# Marvin_1_0.net
KiCad netlist of a schematic drawn in EAGLE
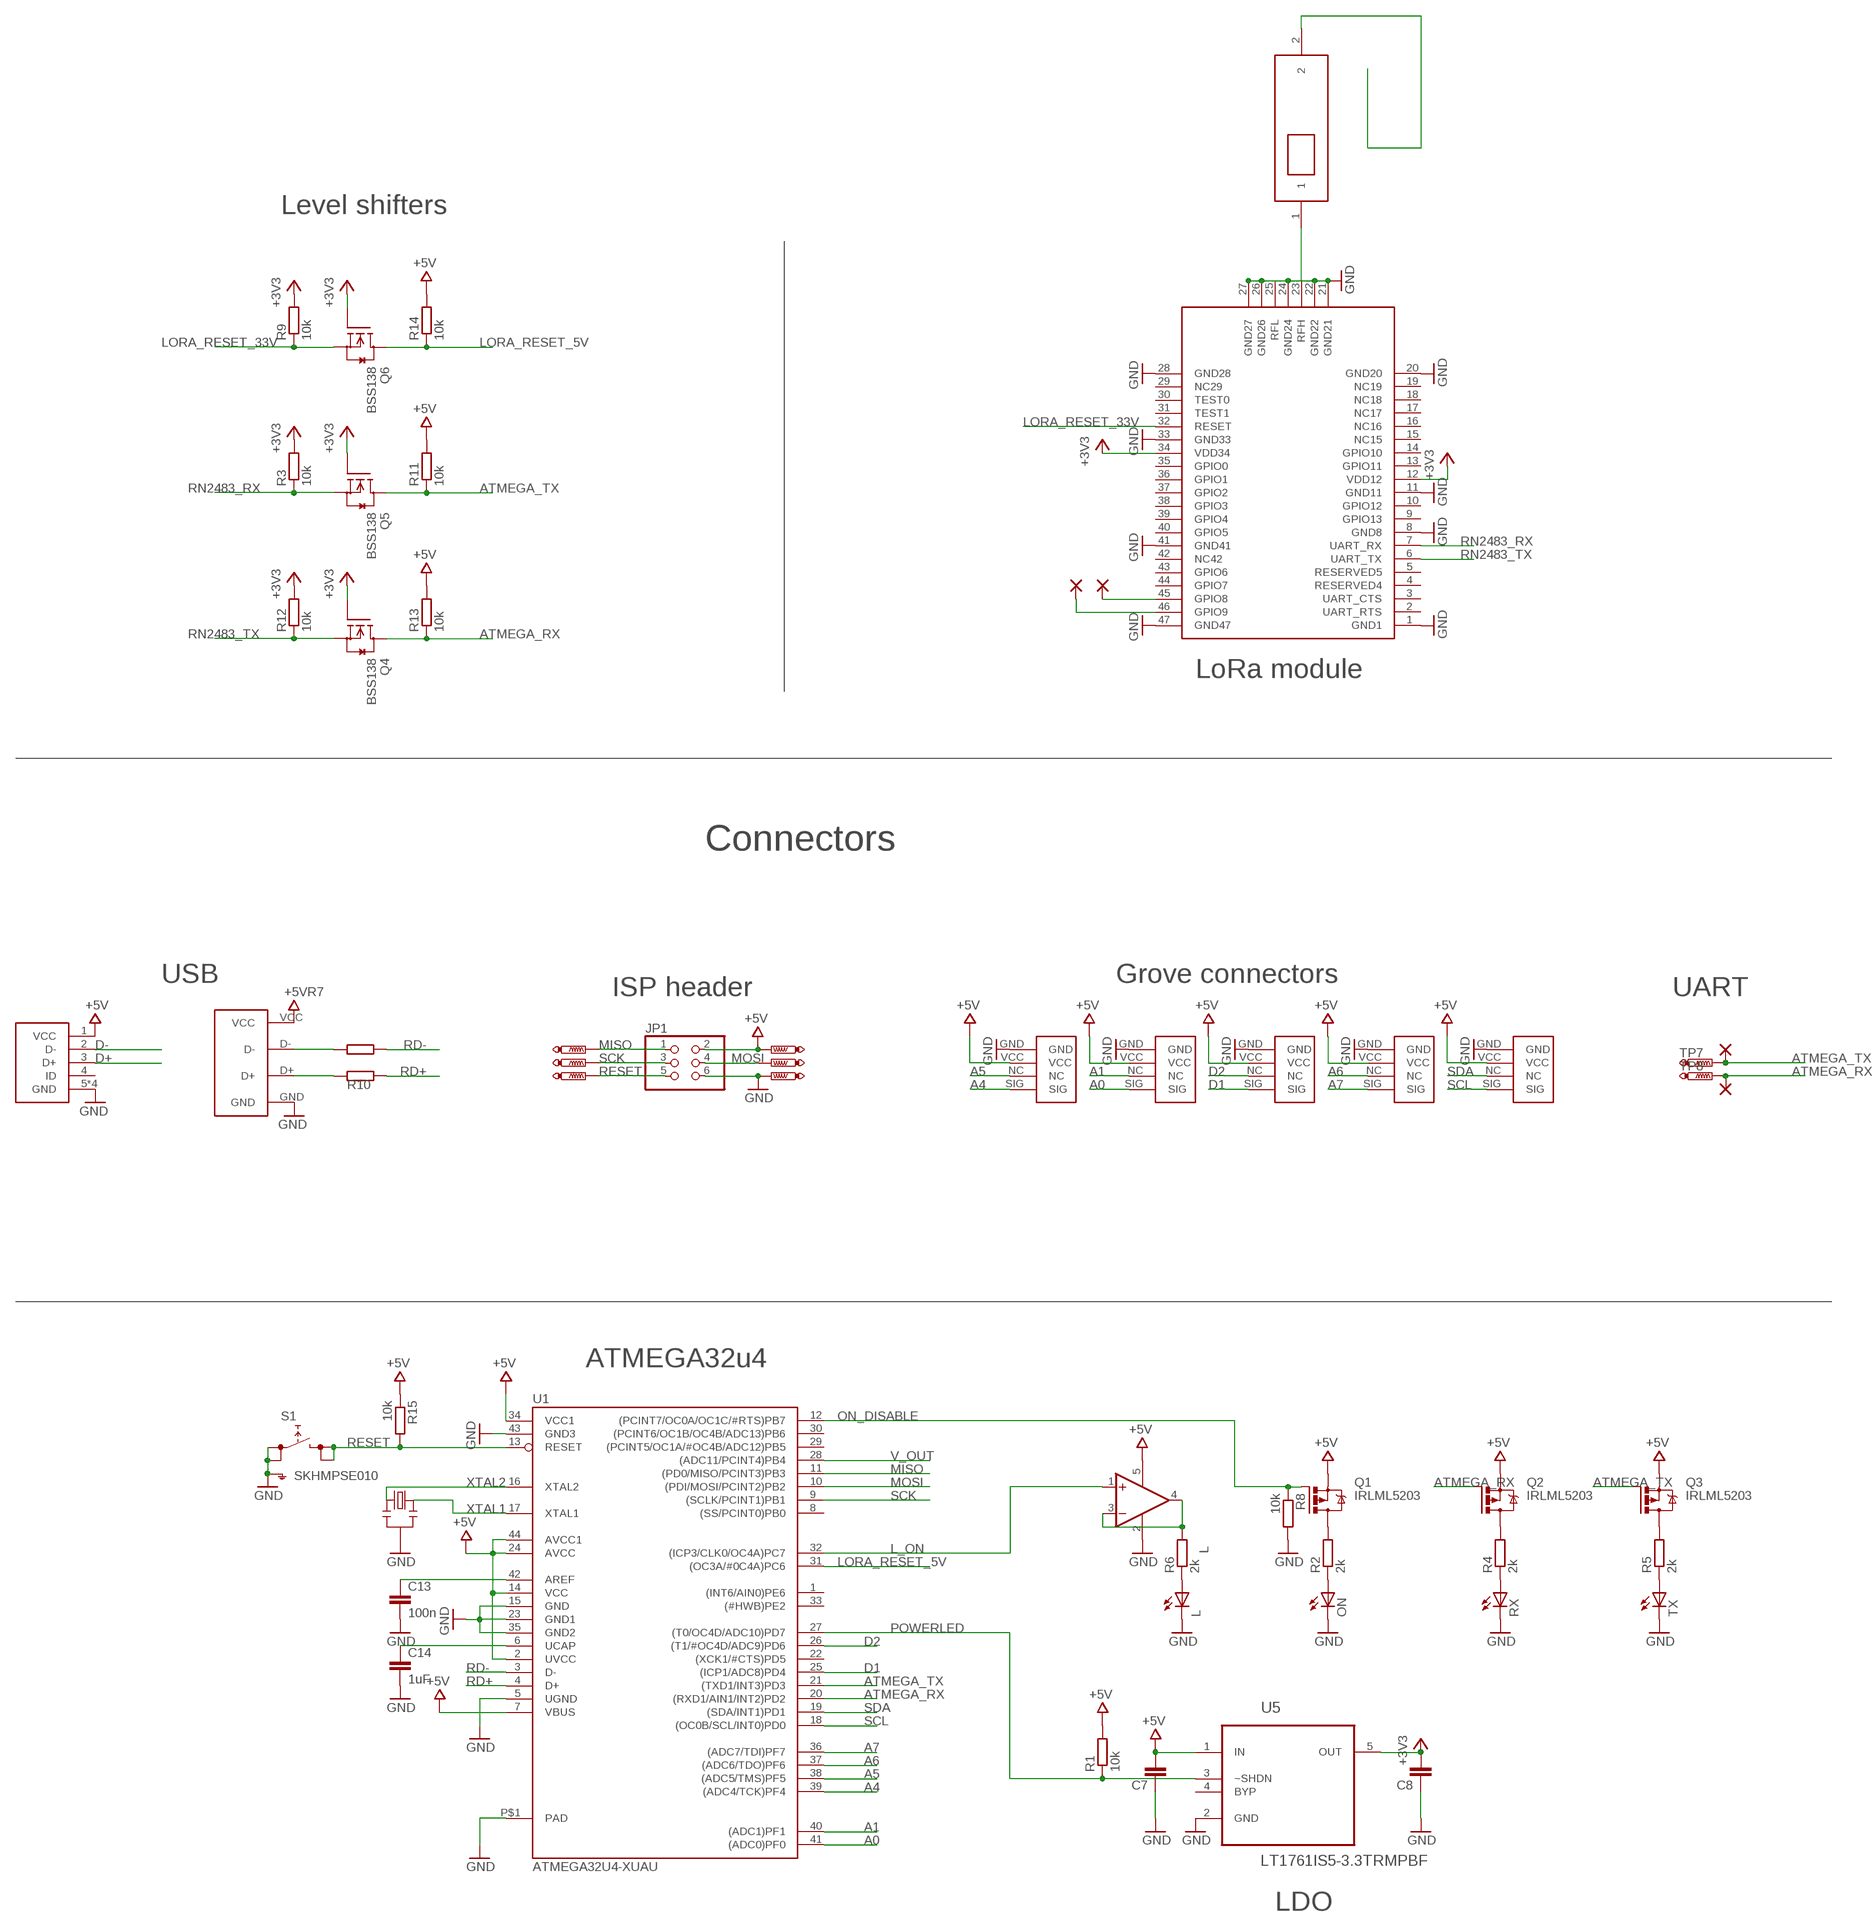
[diagram p0: schematic, sheet 1]

(export (version "E")
  (design (tool "Eeschema 10.0.6"))
  (components
    (comp (ref "A1")
      (value "GROVE")
      (footprint "eagle-import:4POS2MM")
      (libsource (lib "eagle-import") (part "GROVE"))
    )
    (comp (ref "A2")
      (value "GROVE")
      (footprint "eagle-import:4POS2MM")
      (libsource (lib "eagle-import") (part "GROVE"))
    )
    (comp (ref "A3")
      (value "GROVE")
      (footprint "eagle-import:4POS2MM")
      (libsource (lib "eagle-import") (part "GROVE"))
    )
    (comp (ref "C7")
      (value "C-EUC0603")
      (footprint "eagle-import:C0603")
      (libsource (lib "eagle-import") (part "rcl_C-EUC0603"))
    )
    (comp (ref "C8")
      (value "C-EUC0603")
      (footprint "eagle-import:C0603")
      (libsource (lib "eagle-import") (part "rcl_C-EUC0603"))
    )
    (comp (ref "C13")
      (value "100n")
      (footprint "eagle-import:C0603K")
      (libsource (lib "eagle-import") (part "C-EUC0603K"))
    )
    (comp (ref "C14")
      (value "1uF")
      (footprint "eagle-import:C0603K")
      (libsource (lib "eagle-import") (part "C-EUC0603K"))
    )
    (comp (ref "D2")
      (value "GROVE")
      (footprint "eagle-import:4POS2MM")
      (libsource (lib "eagle-import") (part "GROVE"))
    )
    (comp (ref "D2/I2C")
      (value "GROVE")
      (footprint "eagle-import:4POS2MM")
      (libsource (lib "eagle-import") (part "GROVE"))
    )
    (comp (ref "IC1")
      (value "LM321MF")
      (footprint "eagle-import:SOT23-5")
      (libsource (lib "eagle-import") (part "LM321?MF"))
    )
    (comp (ref "JP1")
      (value "PINHD-2X3")
      (footprint "eagle-import:2X03")
      (libsource (lib "eagle-import") (part "PINHD-2X3"))
    )
    (comp (ref "L")
      (value "LEDSML0603")
      (footprint "eagle-import:SML0603")
      (libsource (lib "eagle-import") (part "LEDSML0603"))
    )
    (comp (ref "ON")
      (value "LEDSML0603")
      (footprint "eagle-import:SML0603")
      (libsource (lib "eagle-import") (part "LEDSML0603"))
    )
    (comp (ref "PAD1")
      (value "WIREPAD1,6/0,9")
      (footprint "eagle-import:1,6_0,9")
      (libsource (lib "eagle-import") (part "WIREPAD1,6/0,9"))
    )
    (comp (ref "PAD2")
      (value "WIREPAD1,6/0,9")
      (footprint "eagle-import:1,6_0,9")
      (libsource (lib "eagle-import") (part "WIREPAD1,6/0,9"))
    )
    (comp (ref "PAD3")
      (value "WIREPAD1,6/0,9")
      (footprint "eagle-import:1,6_0,9")
      (libsource (lib "eagle-import") (part "WIREPAD1,6/0,9"))
    )
    (comp (ref "PAD4")
      (value "WIREPAD1,6/0,9")
      (footprint "eagle-import:1,6_0,9")
      (libsource (lib "eagle-import") (part "WIREPAD1,6/0,9"))
    )
    (comp (ref "Q1")
      (value "IRLML5203")
      (footprint "eagle-import:MICRO3")
      (libsource (lib "eagle-import") (part "IRLML5203"))
    )
    (comp (ref "Q2")
      (value "IRLML5203")
      (footprint "eagle-import:MICRO3")
      (libsource (lib "eagle-import") (part "IRLML5203"))
    )
    (comp (ref "Q3")
      (value "IRLML5203")
      (footprint "eagle-import:MICRO3")
      (libsource (lib "eagle-import") (part "IRLML5203"))
    )
    (comp (ref "Q4")
      (value "BSS138")
      (footprint "eagle-import:SOT23")
      (libsource (lib "eagle-import") (part "BSS138"))
    )
    (comp (ref "Q5")
      (value "BSS138")
      (footprint "eagle-import:SOT23")
      (libsource (lib "eagle-import") (part "BSS138"))
    )
    (comp (ref "Q6")
      (value "BSS138")
      (footprint "eagle-import:SOT23")
      (libsource (lib "eagle-import") (part "BSS138"))
    )
    (comp (ref "R1")
      (value "10k")
      (footprint "eagle-import:R0603")
      (libsource (lib "eagle-import") (part "rcl_R-EU_R0603"))
    )
    (comp (ref "R2")
      (value "2k")
      (footprint "eagle-import:R0603")
      (libsource (lib "eagle-import") (part "rcl_R-EU_R0603"))
    )
    (comp (ref "R3")
      (value "10k")
      (footprint "eagle-import:R0603")
      (libsource (lib "eagle-import") (part "rcl_R-EU_R0603"))
    )
    (comp (ref "R4")
      (value "2k")
      (footprint "eagle-import:R0603")
      (libsource (lib "eagle-import") (part "rcl_R-EU_R0603"))
    )
    (comp (ref "R5")
      (value "2k")
      (footprint "eagle-import:R0603")
      (libsource (lib "eagle-import") (part "rcl_R-EU_R0603"))
    )
    (comp (ref "R6")
      (value "2k")
      (footprint "eagle-import:R0603")
      (libsource (lib "eagle-import") (part "rcl_R-EU_R0603"))
    )
    (comp (ref "R7")
      (value "30")
      (footprint "eagle-import:R0603-ROUND")
      (libsource (lib "eagle-import") (part "R-EU_R0603"))
    )
    (comp (ref "R8")
      (value "10k")
      (footprint "eagle-import:R0603")
      (libsource (lib "eagle-import") (part "rcl_R-EU_R0603"))
    )
    (comp (ref "R9")
      (value "10k")
      (footprint "eagle-import:R0603")
      (libsource (lib "eagle-import") (part "rcl_R-EU_R0603"))
    )
    (comp (ref "R10")
      (value "30")
      (footprint "eagle-import:R0603-ROUND")
      (libsource (lib "eagle-import") (part "R-EU_R0603"))
    )
    (comp (ref "R11")
      (value "10k")
      (footprint "eagle-import:R0603")
      (libsource (lib "eagle-import") (part "rcl_R-EU_R0603"))
    )
    (comp (ref "R12")
      (value "10k")
      (footprint "eagle-import:R0603")
      (libsource (lib "eagle-import") (part "rcl_R-EU_R0603"))
    )
    (comp (ref "R13")
      (value "10k")
      (footprint "eagle-import:R0603")
      (libsource (lib "eagle-import") (part "rcl_R-EU_R0603"))
    )
    (comp (ref "R14")
      (value "10k")
      (footprint "eagle-import:R0603")
      (libsource (lib "eagle-import") (part "rcl_R-EU_R0603"))
    )
    (comp (ref "R15")
      (value "10k")
      (footprint "eagle-import:R0603")
      (libsource (lib "eagle-import") (part "rcl_R-EU_R0603"))
    )
    (comp (ref "RX")
      (value "LEDSML0603")
      (footprint "eagle-import:SML0603")
      (libsource (lib "eagle-import") (part "LEDSML0603"))
    )
    (comp (ref "S1")
      (value "SKHMPSE010")
      (footprint "eagle-import:SKHMPXE010")
      (libsource (lib "eagle-import") (part "SKHMPE010S"))
    )
    (comp (ref "TP1")
      (value "PTR1B1,27")
      (footprint "eagle-import:B1,27")
      (libsource (lib "eagle-import") (part "PTR1B1,27"))
    )
    (comp (ref "TP2")
      (value "PTR1B1,27")
      (footprint "eagle-import:B1,27")
      (libsource (lib "eagle-import") (part "PTR1B1,27"))
    )
    (comp (ref "TP3")
      (value "PTR1B1,27")
      (footprint "eagle-import:B1,27")
      (libsource (lib "eagle-import") (part "PTR1B1,27"))
    )
    (comp (ref "TP4")
      (value "PTR1B1,27")
      (footprint "eagle-import:B1,27")
      (libsource (lib "eagle-import") (part "PTR1B1,27"))
    )
    (comp (ref "TP5")
      (value "PTR1B1,27")
      (footprint "eagle-import:B1,27")
      (libsource (lib "eagle-import") (part "PTR1B1,27"))
    )
    (comp (ref "TP6")
      (value "PTR1B1,27")
      (footprint "eagle-import:B1,27")
      (libsource (lib "eagle-import") (part "PTR1B1,27"))
    )
    (comp (ref "TP7")
      (value "PTR1B1,27")
      (footprint "eagle-import:B1,27")
      (libsource (lib "eagle-import") (part "PTR1B1,27"))
    )
    (comp (ref "TP8")
      (value "PTR1B1,27")
      (footprint "eagle-import:B1,27")
      (libsource (lib "eagle-import") (part "PTR1B1,27"))
    )
    (comp (ref "TX")
      (value "LEDSML0603")
      (footprint "eagle-import:SML0603")
      (libsource (lib "eagle-import") (part "LEDSML0603"))
    )
    (comp (ref "U$1")
      (value "RN2483")
      (footprint "eagle-import:RN2483")
      (libsource (lib "eagle-import") (part "RN2483"))
    )
    (comp (ref "U$3")
      (value "USBA")
      (footprint "eagle-import:USBAPLUG")
      (libsource (lib "eagle-import") (part "USBA"))
    )
    (comp (ref "U$16")
      (value "USB-VERTICAL")
      (footprint "eagle-import:MICROUSBVERTICAL")
      (libsource (lib "eagle-import") (part "USB-VERTICAL"))
    )
    (comp (ref "U$25")
      (value "868AT")
      (footprint "eagle-import:868AT")
      (libsource (lib "eagle-import") (part "868AT"))
    )
    (comp (ref "U1")
      (value "ATMEGA32U4-XUAU")
      (footprint "eagle-import:TQFP44-PAD")
      (libsource (lib "eagle-import") (part "ATMEGA32U4-XUAU"))
    )
    (comp (ref "U5")
      (value "LT1761IS5-3.3TRMPBF")
      (footprint "eagle-import:SOT95P280X100-5N")
      (fields (field (name "MPN") "LT1761IS5-3.3#TRMPBF"))
      (libsource (lib "eagle-import") (part "LT1761IS5-3.3TRMPBF"))
    )
    (comp (ref "Y1")
      (value "CSTCE16M0V53-R0 16MHZ")
      (footprint "eagle-import:RESONATOR")
      (libsource (lib "eagle-import") (part "RESONATORMU"))
    )
  )
  (nets
    (net (code "1") (name "+3V3") (class "Default")
      (node (ref "C8") (pin "2") (pinfunction "2_2") (pintype "passive"))
      (node (ref "Q4") (pin "1") (pinfunction "G_1") (pintype "passive"))
      (node (ref "Q5") (pin "1") (pinfunction "G_1") (pintype "passive"))
      (node (ref "Q6") (pin "1") (pinfunction "G_1") (pintype "passive"))
      (node (ref "R12") (pin "2") (pinfunction "2_2") (pintype "passive"))
      (node (ref "R3") (pin "2") (pinfunction "2_2") (pintype "passive"))
      (node (ref "R9") (pin "2") (pinfunction "2_2") (pintype "passive"))
      (node (ref "U$1") (pin "12") (pinfunction "VDD12_12") (pintype "bidirectional"))
      (node (ref "U$1") (pin "34") (pinfunction "VDD34_34") (pintype "bidirectional"))
      (node (ref "U5") (pin "5") (pinfunction "OUT_5") (pintype "output"))
    )
    (net (code "2") (name "+5V") (class "Default")
      (node (ref "A1") (pin "VCC") (pinfunction "VCC_VCC") (pintype "bidirectional"))
      (node (ref "A2") (pin "VCC") (pinfunction "VCC_VCC") (pintype "bidirectional"))
      (node (ref "A3") (pin "VCC") (pinfunction "VCC_VCC") (pintype "bidirectional"))
      (node (ref "C7") (pin "2") (pinfunction "2_2") (pintype "passive"))
      (node (ref "D2") (pin "VCC") (pinfunction "VCC_VCC") (pintype "bidirectional"))
      (node (ref "D2/I2C") (pin "VCC") (pinfunction "VCC_VCC") (pintype "bidirectional"))
      (node (ref "IC1") (pin "5") (pinfunction "V+_5") (pintype "power_in"))
      (node (ref "JP1") (pin "2") (pinfunction "2_2") (pintype "passive"))
      (node (ref "Q1") (pin "2") (pinfunction "S_2") (pintype "passive"))
      (node (ref "Q2") (pin "2") (pinfunction "S_2") (pintype "passive"))
      (node (ref "Q3") (pin "2") (pinfunction "S_2") (pintype "passive"))
      (node (ref "R1") (pin "2") (pinfunction "2_2") (pintype "passive"))
      (node (ref "R11") (pin "2") (pinfunction "2_2") (pintype "passive"))
      (node (ref "R13") (pin "2") (pinfunction "2_2") (pintype "passive"))
      (node (ref "R14") (pin "2") (pinfunction "2_2") (pintype "passive"))
      (node (ref "R15") (pin "1") (pinfunction "1_1") (pintype "passive"))
      (node (ref "TP6") (pin "TP") (pinfunction "TP_TP") (pintype "input"))
      (node (ref "U$16") (pin "1") (pinfunction "VCC_1") (pintype "bidirectional"))
      (node (ref "U$3") (pin "VCC") (pinfunction "VCC_VCC") (pintype "bidirectional"))
      (node (ref "U1") (pin "14") (pinfunction "VCC_14") (pintype "power_in"))
      (node (ref "U1") (pin "2") (pinfunction "UVCC_2") (pintype "power_in"))
      (node (ref "U1") (pin "24") (pinfunction "AVCC_24") (pintype "power_in"))
      (node (ref "U1") (pin "34") (pinfunction "VCC1_34") (pintype "power_in"))
      (node (ref "U1") (pin "44") (pinfunction "AVCC1_44") (pintype "power_in"))
      (node (ref "U1") (pin "7") (pinfunction "VBUS_7") (pintype "input"))
      (node (ref "U5") (pin "1") (pinfunction "IN_1") (pintype "input"))
    )
    (net (code "3") (name "/A0") (class "Default")
      (node (ref "A1") (pin "SIG") (pinfunction "SIG_SIG") (pintype "bidirectional"))
      (node (ref "U1") (pin "41") (pinfunction "(ADC0)PF0_41") (pintype "bidirectional"))
    )
    (net (code "4") (name "/A1") (class "Default")
      (node (ref "A1") (pin "NC") (pinfunction "NC_NC") (pintype "bidirectional"))
      (node (ref "U1") (pin "40") (pinfunction "(ADC1)PF1_40") (pintype "bidirectional"))
    )
    (net (code "5") (name "/A4") (class "Default")
      (node (ref "A2") (pin "SIG") (pinfunction "SIG_SIG") (pintype "bidirectional"))
      (node (ref "U1") (pin "39") (pinfunction "(ADC4/TCK)PF4_39") (pintype "bidirectional"))
    )
    (net (code "6") (name "/A5") (class "Default")
      (node (ref "A2") (pin "NC") (pinfunction "NC_NC") (pintype "bidirectional"))
      (node (ref "U1") (pin "38") (pinfunction "(ADC5/TMS)PF5_38") (pintype "bidirectional"))
    )
    (net (code "7") (name "/A6") (class "Default")
      (node (ref "A3") (pin "NC") (pinfunction "NC_NC") (pintype "bidirectional"))
      (node (ref "U1") (pin "37") (pinfunction "(ADC6/TDO)PF6_37") (pintype "bidirectional"))
    )
    (net (code "8") (name "/A7") (class "Default")
      (node (ref "A3") (pin "SIG") (pinfunction "SIG_SIG") (pintype "bidirectional"))
      (node (ref "U1") (pin "36") (pinfunction "(ADC7/TDI)PF7_36") (pintype "bidirectional"))
    )
    (net (code "9") (name "/ATMEGA_RX") (class "Default")
      (node (ref "PAD2") (pin "1") (pinfunction "P_1") (pintype "passive"))
      (node (ref "Q2") (pin "1") (pinfunction "G_1") (pintype "passive"))
      (node (ref "Q4") (pin "3") (pinfunction "D_3") (pintype "passive"))
      (node (ref "R13") (pin "1") (pinfunction "1_1") (pintype "passive"))
      (node (ref "TP8") (pin "TP") (pinfunction "TP_TP") (pintype "input"))
      (node (ref "U1") (pin "20") (pinfunction "(RXD1/AIN1/INT2)PD2_20") (pintype "bidirectional"))
    )
    (net (code "10") (name "/ATMEGA_TX") (class "Default")
      (node (ref "PAD1") (pin "1") (pinfunction "P_1") (pintype "passive"))
      (node (ref "Q3") (pin "1") (pinfunction "G_1") (pintype "passive"))
      (node (ref "Q5") (pin "3") (pinfunction "D_3") (pintype "passive"))
      (node (ref "R11") (pin "1") (pinfunction "1_1") (pintype "passive"))
      (node (ref "TP7") (pin "TP") (pinfunction "TP_TP") (pintype "input"))
      (node (ref "U1") (pin "21") (pinfunction "(TXD1/INT3)PD3_21") (pintype "bidirectional"))
    )
    (net (code "11") (name "/D+") (class "Default")
      (node (ref "R10") (pin "2") (pinfunction "2_2") (pintype "passive"))
      (node (ref "U$16") (pin "3") (pinfunction "D+_3") (pintype "bidirectional"))
      (node (ref "U$3") (pin "D+") (pinfunction "D+_D+") (pintype "bidirectional"))
    )
    (net (code "12") (name "/D-") (class "Default")
      (node (ref "R7") (pin "2") (pinfunction "2_2") (pintype "passive"))
      (node (ref "U$16") (pin "2") (pinfunction "D-_2") (pintype "bidirectional"))
      (node (ref "U$3") (pin "D-") (pinfunction "D-_D-") (pintype "bidirectional"))
    )
    (net (code "13") (name "/D1") (class "Default")
      (node (ref "D2") (pin "SIG") (pinfunction "SIG_SIG") (pintype "bidirectional"))
      (node (ref "U1") (pin "25") (pinfunction "(ICP1/ADC8)PD4_25") (pintype "bidirectional"))
    )
    (net (code "14") (name "/D2") (class "Default")
      (node (ref "D2") (pin "NC") (pinfunction "NC_NC") (pintype "bidirectional"))
      (node (ref "U1") (pin "26") (pinfunction "(T1/#OC4D/ADC9)PD6_26") (pintype "bidirectional"))
    )
    (net (code "15") (name "/L") (class "Default")
      (node (ref "IC1") (pin "3") (pinfunction "-IN_3") (pintype "input"))
      (node (ref "IC1") (pin "4") (pinfunction "OUT_4") (pintype "output"))
      (node (ref "R6") (pin "2") (pinfunction "2_2") (pintype "passive"))
    )
    (net (code "16") (name "/LORA_RESET_5V") (class "Default")
      (node (ref "Q6") (pin "3") (pinfunction "D_3") (pintype "passive"))
      (node (ref "R14") (pin "1") (pinfunction "1_1") (pintype "passive"))
      (node (ref "U1") (pin "31") (pinfunction "(OC3A/#0C4A)PC6_31") (pintype "bidirectional"))
    )
    (net (code "17") (name "/LORA_RESET_33V") (class "Default")
      (node (ref "Q6") (pin "2") (pinfunction "S_2") (pintype "passive"))
      (node (ref "R9") (pin "1") (pinfunction "1_1") (pintype "passive"))
      (node (ref "U$1") (pin "32") (pinfunction "RESET_32") (pintype "bidirectional"))
    )
    (net (code "18") (name "/L_ON") (class "Default")
      (node (ref "IC1") (pin "1") (pinfunction "+IN_1") (pintype "input"))
      (node (ref "U1") (pin "32") (pinfunction "(ICP3/CLK0/OC4A)PC7_32") (pintype "bidirectional"))
    )
    (net (code "19") (name "/MISO") (class "Default")
      (node (ref "JP1") (pin "1") (pinfunction "1_1") (pintype "passive"))
      (node (ref "TP1") (pin "TP") (pinfunction "TP_TP") (pintype "input"))
      (node (ref "U1") (pin "11") (pinfunction "(PD0/MISO/PCINT3)PB3_11") (pintype "bidirectional"))
    )
    (net (code "20") (name "/MOSI") (class "Default")
      (node (ref "JP1") (pin "4") (pinfunction "4_4") (pintype "passive"))
      (node (ref "TP5") (pin "TP") (pinfunction "TP_TP") (pintype "input"))
      (node (ref "U1") (pin "10") (pinfunction "(PDI/MOSI/PCINT2)PB2_10") (pintype "bidirectional"))
    )
    (net (code "21") (name "/ON_DISABLE") (class "Default")
      (node (ref "Q1") (pin "1") (pinfunction "G_1") (pintype "passive"))
      (node (ref "R8") (pin "1") (pinfunction "1_1") (pintype "passive"))
      (node (ref "U1") (pin "12") (pinfunction "(PCINT7/OC0A/OC1C/#RTS)PB7_12") (pintype "bidirectional"))
    )
    (net (code "22") (name "/POWERLED") (class "Default")
      (node (ref "R1") (pin "1") (pinfunction "1_1") (pintype "passive"))
      (node (ref "U1") (pin "27") (pinfunction "(T0/OC4D/ADC10)PD7_27") (pintype "bidirectional"))
      (node (ref "U5") (pin "3") (pinfunction "~{SHDN}_3") (pintype "input"))
    )
    (net (code "23") (name "/RD+") (class "Default")
      (node (ref "R10") (pin "1") (pinfunction "1_1") (pintype "passive"))
      (node (ref "U1") (pin "4") (pinfunction "D+_4") (pintype "bidirectional"))
    )
    (net (code "24") (name "/RD-") (class "Default")
      (node (ref "R7") (pin "1") (pinfunction "1_1") (pintype "passive"))
      (node (ref "U1") (pin "3") (pinfunction "D-_3") (pintype "bidirectional"))
    )
    (net (code "25") (name "/RESET") (class "Default")
      (node (ref "JP1") (pin "5") (pinfunction "5_5") (pintype "passive"))
      (node (ref "R15") (pin "2") (pinfunction "2_2") (pintype "passive"))
      (node (ref "S1") (pin "3") (pinfunction "2.1_3") (pintype "passive"))
      (node (ref "S1") (pin "4") (pinfunction "2.2_4") (pintype "passive"))
      (node (ref "TP3") (pin "TP") (pinfunction "TP_TP") (pintype "input"))
      (node (ref "U1") (pin "13") (pinfunction "RESET_13") (pintype "input"))
    )
    (net (code "26") (name "/RN2483_RX") (class "Default")
      (node (ref "Q5") (pin "2") (pinfunction "S_2") (pintype "passive"))
      (node (ref "R3") (pin "1") (pinfunction "1_1") (pintype "passive"))
      (node (ref "U$1") (pin "7") (pinfunction "UART_RX_7") (pintype "bidirectional"))
    )
    (net (code "27") (name "/RN2483_TX") (class "Default")
      (node (ref "Q4") (pin "2") (pinfunction "S_2") (pintype "passive"))
      (node (ref "R12") (pin "1") (pinfunction "1_1") (pintype "passive"))
      (node (ref "U$1") (pin "6") (pinfunction "UART_TX_6") (pintype "bidirectional"))
    )
    (net (code "28") (name "/SCK") (class "Default")
      (node (ref "JP1") (pin "3") (pinfunction "3_3") (pintype "passive"))
      (node (ref "TP2") (pin "TP") (pinfunction "TP_TP") (pintype "input"))
      (node (ref "U1") (pin "9") (pinfunction "(SCLK/PCINT1)PB1_9") (pintype "bidirectional"))
    )
    (net (code "29") (name "/SCL") (class "Default")
      (node (ref "D2/I2C") (pin "SIG") (pinfunction "SIG_SIG") (pintype "bidirectional"))
      (node (ref "U1") (pin "18") (pinfunction "(OC0B/SCL/INT0)PD0_18") (pintype "bidirectional"))
    )
    (net (code "30") (name "/SDA") (class "Default")
      (node (ref "D2/I2C") (pin "NC") (pinfunction "NC_NC") (pintype "bidirectional"))
      (node (ref "U1") (pin "19") (pinfunction "(SDA/INT1)PD1_19") (pintype "bidirectional"))
    )
    (net (code "31") (name "/V_OUT") (class "Default")
      (node (ref "U1") (pin "28") (pinfunction "(ADC11/PCINT4)PB4_28") (pintype "bidirectional"))
    )
    (net (code "32") (name "/XTAL1") (class "Default")
      (node (ref "U1") (pin "17") (pinfunction "XTAL1_17") (pintype "bidirectional"))
      (node (ref "Y1") (pin "3") (pinfunction "3_3") (pintype "passive"))
    )
    (net (code "33") (name "/XTAL2") (class "Default")
      (node (ref "U1") (pin "16") (pinfunction "XTAL2_16") (pintype "bidirectional"))
      (node (ref "Y1") (pin "1") (pinfunction "1_1") (pintype "passive"))
    )
    (net (code "34") (name "GND") (class "Default")
      (node (ref "A1") (pin "GND") (pinfunction "GND_GND") (pintype "bidirectional"))
      (node (ref "A2") (pin "GND") (pinfunction "GND_GND") (pintype "bidirectional"))
      (node (ref "A3") (pin "GND") (pinfunction "GND_GND") (pintype "bidirectional"))
      (node (ref "C13") (pin "2") (pinfunction "2_2") (pintype "passive"))
      (node (ref "C14") (pin "2") (pinfunction "2_2") (pintype "passive"))
      (node (ref "C7") (pin "1") (pinfunction "1_1") (pintype "passive"))
      (node (ref "C8") (pin "1") (pinfunction "1_1") (pintype "passive"))
      (node (ref "D2") (pin "GND") (pinfunction "GND_GND") (pintype "bidirectional"))
      (node (ref "D2/I2C") (pin "GND") (pinfunction "GND_GND") (pintype "bidirectional"))
      (node (ref "IC1") (pin "2") (pinfunction "V-_2") (pintype "power_in"))
      (node (ref "JP1") (pin "6") (pinfunction "6_6") (pintype "passive"))
      (node (ref "L") (pin "C") (pinfunction "C_C") (pintype "passive"))
      (node (ref "ON") (pin "C") (pinfunction "C_C") (pintype "passive"))
      (node (ref "R8") (pin "2") (pinfunction "2_2") (pintype "passive"))
      (node (ref "RX") (pin "C") (pinfunction "C_C") (pintype "passive"))
      (node (ref "S1") (pin "1") (pinfunction "1.1_1") (pintype "passive"))
      (node (ref "S1") (pin "2") (pinfunction "1.2_2") (pintype "passive"))
      (node (ref "S1") (pin "5") (pinfunction "SH_5") (pintype "passive"))
      (node (ref "TP4") (pin "TP") (pinfunction "TP_TP") (pintype "input"))
      (node (ref "TX") (pin "C") (pinfunction "C_C") (pintype "passive"))
      (node (ref "U$1") (pin "1") (pinfunction "GND1_1") (pintype "bidirectional"))
      (node (ref "U$1") (pin "11") (pinfunction "GND11_11") (pintype "bidirectional"))
      (node (ref "U$1") (pin "20") (pinfunction "GND20_20") (pintype "bidirectional"))
      (node (ref "U$1") (pin "21") (pinfunction "GND21_21") (pintype "bidirectional"))
      (node (ref "U$1") (pin "22") (pinfunction "GND22_22") (pintype "bidirectional"))
      (node (ref "U$1") (pin "24") (pinfunction "GND24_24") (pintype "bidirectional"))
      (node (ref "U$1") (pin "26") (pinfunction "GND26_26") (pintype "bidirectional"))
      (node (ref "U$1") (pin "27") (pinfunction "GND27_27") (pintype "bidirectional"))
      (node (ref "U$1") (pin "28") (pinfunction "GND28_28") (pintype "bidirectional"))
      (node (ref "U$1") (pin "33") (pinfunction "GND33_33") (pintype "bidirectional"))
      (node (ref "U$1") (pin "41") (pinfunction "GND41_41") (pintype "bidirectional"))
      (node (ref "U$1") (pin "47") (pinfunction "GND47_47") (pintype "bidirectional"))
      (node (ref "U$1") (pin "8") (pinfunction "GND8_8") (pintype "bidirectional"))
      (node (ref "U$16") (pin "5") (pinfunction "GND_5") (pintype "bidirectional"))
      (node (ref "U$16") (pin "P$1") (pinfunction "GND_P$1") (pintype "bidirectional"))
      (node (ref "U$16") (pin "P$2") (pinfunction "GND_P$2") (pintype "bidirectional"))
      (node (ref "U$16") (pin "P$3") (pinfunction "GND_P$3") (pintype "bidirectional"))
      (node (ref "U$3") (pin "GND") (pinfunction "GND_GND") (pintype "bidirectional"))
      (node (ref "U1") (pin "15") (pinfunction "GND_15") (pintype "power_in"))
      (node (ref "U1") (pin "23") (pinfunction "GND1_23") (pintype "power_in"))
      (node (ref "U1") (pin "35") (pinfunction "GND2_35") (pintype "power_in"))
      (node (ref "U1") (pin "43") (pinfunction "GND3_43") (pintype "power_in"))
      (node (ref "U1") (pin "5") (pinfunction "UGND_5") (pintype "power_in"))
      (node (ref "U1") (pin "P$1") (pinfunction "PAD_P$1") (pintype "power_in"))
      (node (ref "U5") (pin "2") (pinfunction "GND_2") (pintype "passive"))
      (node (ref "Y1") (pin "2") (pinfunction "2_2") (pintype "passive"))
    )
    (net (code "35") (name "Net-(L-PadA)") (class "Default")
      (node (ref "L") (pin "A") (pinfunction "A_A") (pintype "passive"))
      (node (ref "R6") (pin "1") (pinfunction "1_1") (pintype "passive"))
    )
    (net (code "36") (name "Net-(ON-PadA)") (class "Default")
      (node (ref "ON") (pin "A") (pinfunction "A_A") (pintype "passive"))
      (node (ref "R2") (pin "1") (pinfunction "1_1") (pintype "passive"))
    )
    (net (code "37") (name "Net-(PAD3-P)") (class "Default")
      (node (ref "PAD3") (pin "1") (pinfunction "P_1") (pintype "passive"))
      (node (ref "U$1") (pin "46") (pinfunction "GPIO9_46") (pintype "bidirectional"))
    )
    (net (code "38") (name "Net-(PAD4-P)") (class "Default")
      (node (ref "PAD4") (pin "1") (pinfunction "P_1") (pintype "passive"))
      (node (ref "U$1") (pin "45") (pinfunction "GPIO8_45") (pintype "bidirectional"))
    )
    (net (code "39") (name "Net-(Q1-D)") (class "Default")
      (node (ref "Q1") (pin "3") (pinfunction "D_3") (pintype "passive"))
      (node (ref "R2") (pin "2") (pinfunction "2_2") (pintype "passive"))
    )
    (net (code "40") (name "Net-(Q2-D)") (class "Default")
      (node (ref "Q2") (pin "3") (pinfunction "D_3") (pintype "passive"))
      (node (ref "R4") (pin "2") (pinfunction "2_2") (pintype "passive"))
    )
    (net (code "41") (name "Net-(Q3-D)") (class "Default")
      (node (ref "Q3") (pin "3") (pinfunction "D_3") (pintype "passive"))
      (node (ref "R5") (pin "2") (pinfunction "2_2") (pintype "passive"))
    )
    (net (code "42") (name "Net-(R4-Pad1)") (class "Default")
      (node (ref "R4") (pin "1") (pinfunction "1_1") (pintype "passive"))
      (node (ref "RX") (pin "A") (pinfunction "A_A") (pintype "passive"))
    )
    (net (code "43") (name "Net-(R5-Pad1)") (class "Default")
      (node (ref "R5") (pin "1") (pinfunction "1_1") (pintype "passive"))
      (node (ref "TX") (pin "A") (pinfunction "A_A") (pintype "passive"))
    )
    (net (code "44") (name "Net-(U$1-RFH)") (class "Default")
      (node (ref "U$1") (pin "23") (pinfunction "RFH_23") (pintype "bidirectional"))
      (node (ref "U$25") (pin "1") (pinfunction "1_1") (pintype "bidirectional"))
    )
    (net (code "45") (name "Net-(U1-AREF)") (class "Default")
      (node (ref "C13") (pin "1") (pinfunction "1_1") (pintype "passive"))
      (node (ref "U1") (pin "42") (pinfunction "AREF_42") (pintype "power_in"))
    )
    (net (code "46") (name "Net-(U1-UCAP)") (class "Default")
      (node (ref "C14") (pin "1") (pinfunction "1_1") (pintype "passive"))
      (node (ref "U1") (pin "6") (pinfunction "UCAP_6") (pintype "passive"))
    )
    (net (code "47") (name "unconnected-(U$1-GPIO0-Pad35)") (class "Default")
      (node (ref "U$1") (pin "35") (pinfunction "GPIO0_35") (pintype "bidirectional"))
    )
    (net (code "48") (name "unconnected-(U$1-GPIO1-Pad36)") (class "Default")
      (node (ref "U$1") (pin "36") (pinfunction "GPIO1_36") (pintype "bidirectional"))
    )
    (net (code "49") (name "unconnected-(U$1-GPIO2-Pad37)") (class "Default")
      (node (ref "U$1") (pin "37") (pinfunction "GPIO2_37") (pintype "bidirectional"))
    )
    (net (code "50") (name "unconnected-(U$1-GPIO3-Pad38)") (class "Default")
      (node (ref "U$1") (pin "38") (pinfunction "GPIO3_38") (pintype "bidirectional"))
    )
    (net (code "51") (name "unconnected-(U$1-GPIO4-Pad39)") (class "Default")
      (node (ref "U$1") (pin "39") (pinfunction "GPIO4_39") (pintype "bidirectional"))
    )
    (net (code "52") (name "unconnected-(U$1-GPIO5-Pad40)") (class "Default")
      (node (ref "U$1") (pin "40") (pinfunction "GPIO5_40") (pintype "bidirectional"))
    )
    (net (code "53") (name "unconnected-(U$1-GPIO6-Pad43)") (class "Default")
      (node (ref "U$1") (pin "43") (pinfunction "GPIO6_43") (pintype "bidirectional"))
    )
    (net (code "54") (name "unconnected-(U$1-GPIO7-Pad44)") (class "Default")
      (node (ref "U$1") (pin "44") (pinfunction "GPIO7_44") (pintype "bidirectional"))
    )
    (net (code "55") (name "unconnected-(U$1-GPIO10-Pad14)") (class "Default")
      (node (ref "U$1") (pin "14") (pinfunction "GPIO10_14") (pintype "bidirectional"))
    )
    (net (code "56") (name "unconnected-(U$1-GPIO11-Pad13)") (class "Default")
      (node (ref "U$1") (pin "13") (pinfunction "GPIO11_13") (pintype "bidirectional"))
    )
    (net (code "57") (name "unconnected-(U$1-GPIO12-Pad10)") (class "Default")
      (node (ref "U$1") (pin "10") (pinfunction "GPIO12_10") (pintype "bidirectional"))
    )
    (net (code "58") (name "unconnected-(U$1-GPIO13-Pad9)") (class "Default")
      (node (ref "U$1") (pin "9") (pinfunction "GPIO13_9") (pintype "bidirectional"))
    )
    (net (code "59") (name "unconnected-(U$1-NC15-Pad15)") (class "Default")
      (node (ref "U$1") (pin "15") (pinfunction "NC15_15") (pintype "bidirectional"))
    )
    (net (code "60") (name "unconnected-(U$1-NC16-Pad16)") (class "Default")
      (node (ref "U$1") (pin "16") (pinfunction "NC16_16") (pintype "bidirectional"))
    )
    (net (code "61") (name "unconnected-(U$1-NC17-Pad17)") (class "Default")
      (node (ref "U$1") (pin "17") (pinfunction "NC17_17") (pintype "bidirectional"))
    )
    (net (code "62") (name "unconnected-(U$1-NC18-Pad18)") (class "Default")
      (node (ref "U$1") (pin "18") (pinfunction "NC18_18") (pintype "bidirectional"))
    )
    (net (code "63") (name "unconnected-(U$1-NC19-Pad19)") (class "Default")
      (node (ref "U$1") (pin "19") (pinfunction "NC19_19") (pintype "bidirectional"))
    )
    (net (code "64") (name "unconnected-(U$1-NC29-Pad29)") (class "Default")
      (node (ref "U$1") (pin "29") (pinfunction "NC29_29") (pintype "bidirectional"))
    )
    (net (code "65") (name "unconnected-(U$1-NC42-Pad42)") (class "Default")
      (node (ref "U$1") (pin "42") (pinfunction "NC42_42") (pintype "bidirectional"))
    )
    (net (code "66") (name "unconnected-(U$1-RESERVED4-Pad4)") (class "Default")
      (node (ref "U$1") (pin "4") (pinfunction "RESERVED4_4") (pintype "bidirectional"))
    )
    (net (code "67") (name "unconnected-(U$1-RESERVED5-Pad5)") (class "Default")
      (node (ref "U$1") (pin "5") (pinfunction "RESERVED5_5") (pintype "bidirectional"))
    )
    (net (code "68") (name "unconnected-(U$1-RFL-Pad25)") (class "Default")
      (node (ref "U$1") (pin "25") (pinfunction "RFL_25") (pintype "bidirectional"))
    )
    (net (code "69") (name "unconnected-(U$1-TEST0-Pad30)") (class "Default")
      (node (ref "U$1") (pin "30") (pinfunction "TEST0_30") (pintype "bidirectional"))
    )
    (net (code "70") (name "unconnected-(U$1-TEST1-Pad31)") (class "Default")
      (node (ref "U$1") (pin "31") (pinfunction "TEST1_31") (pintype "bidirectional"))
    )
    (net (code "71") (name "unconnected-(U$1-UART_CTS-Pad3)") (class "Default")
      (node (ref "U$1") (pin "3") (pinfunction "UART_CTS_3") (pintype "bidirectional"))
    )
    (net (code "72") (name "unconnected-(U$1-UART_RTS-Pad2)") (class "Default")
      (node (ref "U$1") (pin "2") (pinfunction "UART_RTS_2") (pintype "bidirectional"))
    )
    (net (code "73") (name "unconnected-(U$16-ID-Pad4)") (class "Default")
      (node (ref "U$16") (pin "4") (pinfunction "ID_4") (pintype "bidirectional"))
    )
    (net (code "74") (name "unconnected-(U$25-Pad2)") (class "Default")
      (node (ref "U$25") (pin "2") (pinfunction "2_2") (pintype "bidirectional"))
    )
    (net (code "75") (name "unconnected-(U1-(#HWB)PE2-Pad33)") (class "Default")
      (node (ref "U1") (pin "33") (pinfunction "(#HWB)PE2_33") (pintype "bidirectional"))
    )
    (net (code "76") (name "unconnected-(U1-(INT6{slash}AIN0)PE6-Pad1)") (class "Default")
      (node (ref "U1") (pin "1") (pinfunction "(INT6/AIN0)PE6_1") (pintype "bidirectional"))
    )
    (net (code "77") (name "unconnected-(U1-(PCINT5{slash}OC1A{slash}#OC4B{slash}ADC12)PB5-Pad29)") (class "Default")
      (node (ref "U1") (pin "29") (pinfunction "(PCINT5/OC1A/#OC4B/ADC12)PB5_29") (pintype "bidirectional"))
    )
    (net (code "78") (name "unconnected-(U1-(PCINT6{slash}OC1B{slash}OC4B{slash}ADC13)PB6-Pad30)") (class "Default")
      (node (ref "U1") (pin "30") (pinfunction "(PCINT6/OC1B/OC4B/ADC13)PB6_30") (pintype "bidirectional"))
    )
    (net (code "79") (name "unconnected-(U1-(SS{slash}PCINT0)PB0-Pad8)") (class "Default")
      (node (ref "U1") (pin "8") (pinfunction "(SS/PCINT0)PB0_8") (pintype "bidirectional"))
    )
    (net (code "80") (name "unconnected-(U1-(XCK1{slash}#CTS)PD5-Pad22)") (class "Default")
      (node (ref "U1") (pin "22") (pinfunction "(XCK1/#CTS)PD5_22") (pintype "bidirectional"))
    )
    (net (code "81") (name "unconnected-(U5-BYP-Pad4)") (class "Default")
      (node (ref "U5") (pin "4") (pinfunction "BYP_4") (pintype "passive"))
    )
  )
)
